# ir_nec.net
KiCad netlist of a schematic drawn in EAGLE
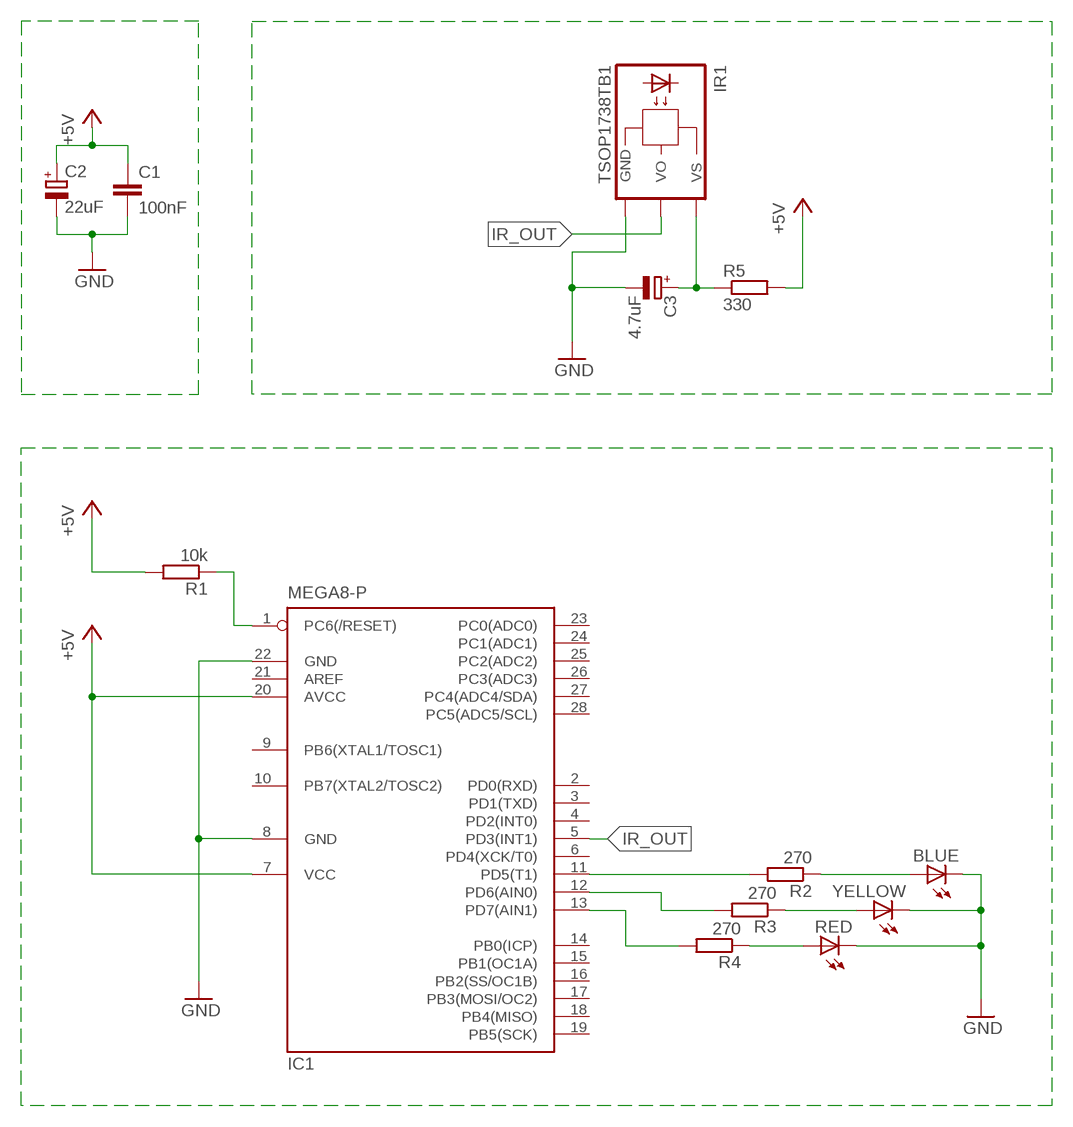
[diagram p0: schematic, sheet 1]

(export (version "E")
  (design (tool "Eeschema 10.0.6"))
  (components
    (comp (ref "BLUE")
      (value "LED3MM")
      (footprint "eagle-import:LED3MM")
      (libsource (lib "eagle-import") (part "LED3MM"))
    )
    (comp (ref "C1")
      (value "100nF")
      (footprint "eagle-import:C050-024X044")
      (libsource (lib "eagle-import") (part "C-EU050-024X044"))
    )
    (comp (ref "C2")
      (value "22uF")
      (footprint "eagle-import:E5-8,5")
      (libsource (lib "eagle-import") (part "CPOL-EUE5-8.5"))
    )
    (comp (ref "C3")
      (value "4.7uF")
      (footprint "eagle-import:E5-8,5")
      (libsource (lib "eagle-import") (part "CPOL-EUE5-8.5"))
    )
    (comp (ref "IC1")
      (value "MEGA8-P")
      (footprint "eagle-import:DIL28-3")
      (libsource (lib "eagle-import") (part "MEGA8-P"))
    )
    (comp (ref "IR1")
      (value "TSOP1738TB1")
      (footprint "eagle-import:TSOP17_TB1")
      (libsource (lib "eagle-import") (part "TSOP17TB138"))
    )
    (comp (ref "R1")
      (value "10k")
      (footprint "eagle-import:0204_7")
      (libsource (lib "eagle-import") (part "R-EU_0204/7"))
    )
    (comp (ref "R2")
      (value "270")
      (footprint "eagle-import:0204_7")
      (libsource (lib "eagle-import") (part "R-EU_0204/7"))
    )
    (comp (ref "R3")
      (value "270")
      (footprint "eagle-import:0204_7")
      (libsource (lib "eagle-import") (part "R-EU_0204/7"))
    )
    (comp (ref "R4")
      (value "270")
      (footprint "eagle-import:0204_7")
      (libsource (lib "eagle-import") (part "R-EU_0204/7"))
    )
    (comp (ref "R5")
      (value "330")
      (footprint "eagle-import:0204_7")
      (libsource (lib "eagle-import") (part "R-EU_0204/7"))
    )
    (comp (ref "RED")
      (value "LED3MM")
      (footprint "eagle-import:LED3MM")
      (libsource (lib "eagle-import") (part "LED3MM"))
    )
    (comp (ref "YELLOW")
      (value "LED3MM")
      (footprint "eagle-import:LED3MM")
      (libsource (lib "eagle-import") (part "LED3MM"))
    )
  )
  (nets
    (net (code "1") (name "+5V") (class "Default")
      (node (ref "C1") (pin "1") (pinfunction "1_1") (pintype "passive"))
      (node (ref "C2") (pin "+") (pinfunction "+_+") (pintype "passive"))
      (node (ref "IC1") (pin "20") (pinfunction "AVCC_20") (pintype "power_in"))
      (node (ref "IC1") (pin "7") (pinfunction "VCC_7") (pintype "power_in"))
      (node (ref "R1") (pin "2") (pinfunction "2_2") (pintype "passive"))
      (node (ref "R5") (pin "2") (pinfunction "2_2") (pintype "passive"))
    )
    (net (code "2") (name "GND") (class "Default")
      (node (ref "BLUE") (pin "K") (pinfunction "C_K") (pintype "passive"))
      (node (ref "C1") (pin "2") (pinfunction "2_2") (pintype "passive"))
      (node (ref "C2") (pin "-") (pinfunction "-_-") (pintype "passive"))
      (node (ref "C3") (pin "-") (pinfunction "-_-") (pintype "passive"))
      (node (ref "IC1") (pin "22") (pinfunction "GND_22") (pintype "power_in"))
      (node (ref "IC1") (pin "8") (pinfunction "GND_8") (pintype "power_in"))
      (node (ref "IR1") (pin "GND") (pinfunction "GND_GND") (pintype "power_in"))
      (node (ref "RED") (pin "K") (pinfunction "C_K") (pintype "passive"))
      (node (ref "YELLOW") (pin "K") (pinfunction "C_K") (pintype "passive"))
    )
    (net (code "3") (name "IR_OUT") (class "Default")
      (node (ref "IC1") (pin "5") (pinfunction "PD3(INT1)_5") (pintype "bidirectional"))
      (node (ref "IR1") (pin "VO") (pinfunction "VO_VO") (pintype "open_collector"))
    )
    (net (code "4") (name "Net-(BLUE-PadA)") (class "Default")
      (node (ref "BLUE") (pin "A") (pinfunction "A_A") (pintype "passive"))
      (node (ref "R2") (pin "1") (pinfunction "1_1") (pintype "passive"))
    )
    (net (code "5") (name "Net-(C3-Pad+)") (class "Default")
      (node (ref "C3") (pin "+") (pinfunction "+_+") (pintype "passive"))
      (node (ref "IR1") (pin "VS") (pinfunction "VS_VS") (pintype "power_in"))
      (node (ref "R5") (pin "1") (pinfunction "1_1") (pintype "passive"))
    )
    (net (code "6") (name "Net-(IC1-PC6({slash}RESET))") (class "Default")
      (node (ref "IC1") (pin "1") (pinfunction "PC6(/RESET)_1") (pintype "bidirectional"))
      (node (ref "R1") (pin "1") (pinfunction "1_1") (pintype "passive"))
    )
    (net (code "7") (name "Net-(IC1-PD5(T1))") (class "Default")
      (node (ref "IC1") (pin "11") (pinfunction "PD5(T1)_11") (pintype "bidirectional"))
      (node (ref "R2") (pin "2") (pinfunction "2_2") (pintype "passive"))
    )
    (net (code "8") (name "Net-(IC1-PD6(AIN0))") (class "Default")
      (node (ref "IC1") (pin "12") (pinfunction "PD6(AIN0)_12") (pintype "bidirectional"))
      (node (ref "R3") (pin "2") (pinfunction "2_2") (pintype "passive"))
    )
    (net (code "9") (name "Net-(IC1-PD7(AIN1))") (class "Default")
      (node (ref "IC1") (pin "13") (pinfunction "PD7(AIN1)_13") (pintype "bidirectional"))
      (node (ref "R4") (pin "2") (pinfunction "2_2") (pintype "passive"))
    )
    (net (code "10") (name "Net-(R3-Pad1)") (class "Default")
      (node (ref "R3") (pin "1") (pinfunction "1_1") (pintype "passive"))
      (node (ref "YELLOW") (pin "A") (pinfunction "A_A") (pintype "passive"))
    )
    (net (code "11") (name "Net-(R4-Pad1)") (class "Default")
      (node (ref "R4") (pin "1") (pinfunction "1_1") (pintype "passive"))
      (node (ref "RED") (pin "A") (pinfunction "A_A") (pintype "passive"))
    )
    (net (code "12") (name "unconnected-(IC1-AREF-Pad21)") (class "Default")
      (node (ref "IC1") (pin "21") (pinfunction "AREF_21") (pintype "passive"))
    )
    (net (code "13") (name "unconnected-(IC1-PB0(ICP)-Pad14)") (class "Default")
      (node (ref "IC1") (pin "14") (pinfunction "PB0(ICP)_14") (pintype "bidirectional"))
    )
    (net (code "14") (name "unconnected-(IC1-PB1(OC1A)-Pad15)") (class "Default")
      (node (ref "IC1") (pin "15") (pinfunction "PB1(OC1A)_15") (pintype "bidirectional"))
    )
    (net (code "15") (name "unconnected-(IC1-PB2(SS{slash}OC1B)-Pad16)") (class "Default")
      (node (ref "IC1") (pin "16") (pinfunction "PB2(SS/OC1B)_16") (pintype "bidirectional"))
    )
    (net (code "16") (name "unconnected-(IC1-PB3(MOSI{slash}OC2)-Pad17)") (class "Default")
      (node (ref "IC1") (pin "17") (pinfunction "PB3(MOSI/OC2)_17") (pintype "bidirectional"))
    )
    (net (code "17") (name "unconnected-(IC1-PB4(MISO)-Pad18)") (class "Default")
      (node (ref "IC1") (pin "18") (pinfunction "PB4(MISO)_18") (pintype "bidirectional"))
    )
    (net (code "18") (name "unconnected-(IC1-PB5(SCK)-Pad19)") (class "Default")
      (node (ref "IC1") (pin "19") (pinfunction "PB5(SCK)_19") (pintype "bidirectional"))
    )
    (net (code "19") (name "unconnected-(IC1-PB6(XTAL1{slash}TOSC1)-Pad9)") (class "Default")
      (node (ref "IC1") (pin "9") (pinfunction "PB6(XTAL1/TOSC1)_9") (pintype "bidirectional"))
    )
    (net (code "20") (name "unconnected-(IC1-PB7(XTAL2{slash}TOSC2)-Pad10)") (class "Default")
      (node (ref "IC1") (pin "10") (pinfunction "PB7(XTAL2/TOSC2)_10") (pintype "bidirectional"))
    )
    (net (code "21") (name "unconnected-(IC1-PC0(ADC0)-Pad23)") (class "Default")
      (node (ref "IC1") (pin "23") (pinfunction "PC0(ADC0)_23") (pintype "bidirectional"))
    )
    (net (code "22") (name "unconnected-(IC1-PC1(ADC1)-Pad24)") (class "Default")
      (node (ref "IC1") (pin "24") (pinfunction "PC1(ADC1)_24") (pintype "bidirectional"))
    )
    (net (code "23") (name "unconnected-(IC1-PC2(ADC2)-Pad25)") (class "Default")
      (node (ref "IC1") (pin "25") (pinfunction "PC2(ADC2)_25") (pintype "bidirectional"))
    )
    (net (code "24") (name "unconnected-(IC1-PC3(ADC3)-Pad26)") (class "Default")
      (node (ref "IC1") (pin "26") (pinfunction "PC3(ADC3)_26") (pintype "bidirectional"))
    )
    (net (code "25") (name "unconnected-(IC1-PC4(ADC4{slash}SDA)-Pad27)") (class "Default")
      (node (ref "IC1") (pin "27") (pinfunction "PC4(ADC4/SDA)_27") (pintype "bidirectional"))
    )
    (net (code "26") (name "unconnected-(IC1-PC5(ADC5{slash}SCL)-Pad28)") (class "Default")
      (node (ref "IC1") (pin "28") (pinfunction "PC5(ADC5/SCL)_28") (pintype "bidirectional"))
    )
    (net (code "27") (name "unconnected-(IC1-PD0(RXD)-Pad2)") (class "Default")
      (node (ref "IC1") (pin "2") (pinfunction "PD0(RXD)_2") (pintype "bidirectional"))
    )
    (net (code "28") (name "unconnected-(IC1-PD1(TXD)-Pad3)") (class "Default")
      (node (ref "IC1") (pin "3") (pinfunction "PD1(TXD)_3") (pintype "bidirectional"))
    )
    (net (code "29") (name "unconnected-(IC1-PD2(INT0)-Pad4)") (class "Default")
      (node (ref "IC1") (pin "4") (pinfunction "PD2(INT0)_4") (pintype "bidirectional"))
    )
    (net (code "30") (name "unconnected-(IC1-PD4(XCK{slash}T0)-Pad6)") (class "Default")
      (node (ref "IC1") (pin "6") (pinfunction "PD4(XCK/T0)_6") (pintype "bidirectional"))
    )
  )
)
